# PowerAmplifier.net
KiCad netlist of a schematic drawn in Altium Designer
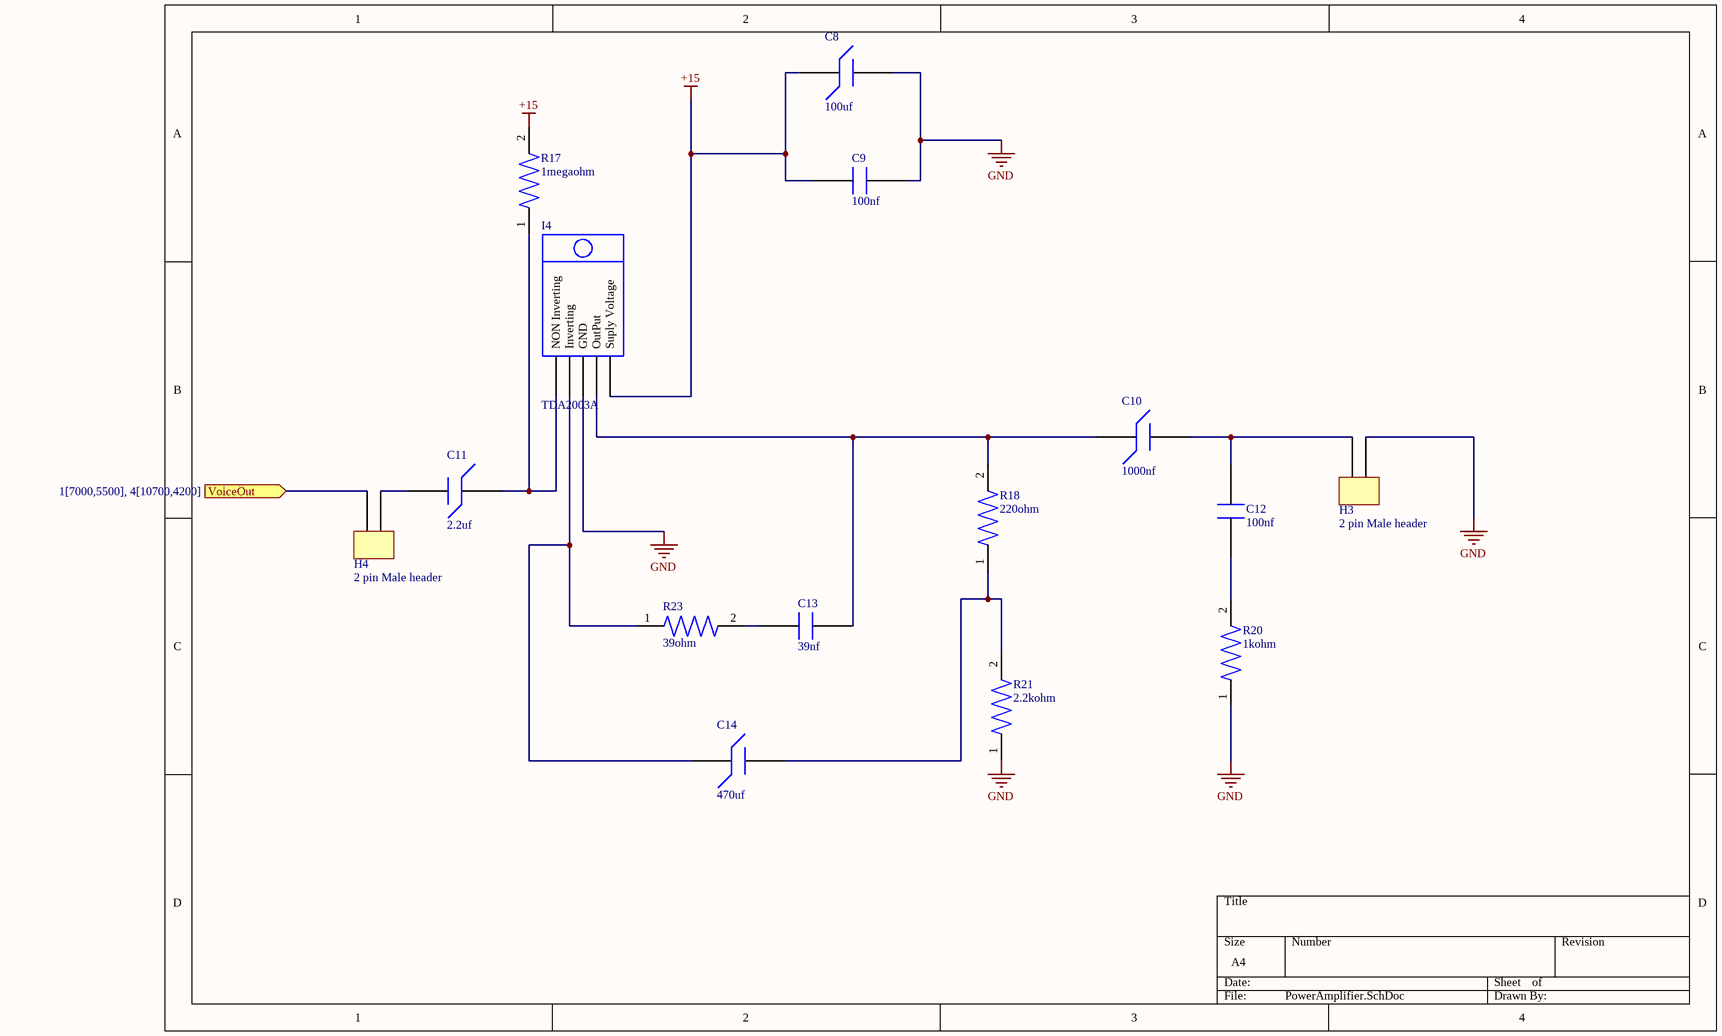
[diagram p0: PowerAmplifier.SchDoc]

(export (version "E")
  (design (tool "Eeschema 10.0.6"))
  (components
    (comp (ref "C8")
      (value "100uf")
      (footprint "Capasitor")
      (fields
        (field (name "MANUFACTURER") "Rubycon")
        (field (name "MANUFACTURER PART NUMBER") "35ZLH100MEFC6.3X11")
      )
      (libsource (lib "AudioAmplifierBasic") (part "35ZLH100MEFC6.3X11"))
    )
    (comp (ref "C9")
      (value "100nf")
      (footprint "ceramic Capacitor")
      (fields
        (field (name "MANUFACTURER") "Vishay BCcomponents")
        (field (name "MANUFACTURER PART NUMBER") "K104K20X7RK53H5G")
      )
      (libsource (lib "AudioAmplifierBasic") (part "K104K20X7RK53H5G"))
    )
    (comp (ref "C10")
      (value "1000nf")
      (footprint "Capasitor")
      (fields
        (field (name "MANUFACTURER") "Rubycon")
        (field (name "MANUFACTURER PART NUMBER") "10ZLH1000MEFC10X12.5")
      )
      (libsource (lib "AudioAmplifierBasic") (part "10ZLH1000MEFC10X12.5"))
    )
    (comp (ref "C11")
      (value "2.2uf")
      (footprint "Capasitor")
      (fields
        (field (name "MANUFACTURER") "Rubycon")
        (field (name "MANUFACTURER PART NUMBER") "400LLE2R2MEFC8X11.5")
      )
      (libsource (lib "AudioAmplifierBasic") (part "400LLE2R2MEFC8X11.5"))
    )
    (comp (ref "C12")
      (value "100nf")
      (footprint "ceramic Capacitor")
      (fields
        (field (name "MANUFACTURER") "Vishay BCcomponents")
        (field (name "MANUFACTURER PART NUMBER") "K104K20X7RK53H5G")
      )
      (libsource (lib "AudioAmplifierBasic") (part "K104K20X7RK53H5G"))
    )
    (comp (ref "C13")
      (value "39nf")
      (footprint "Ceramic Capacitor 2")
      (fields
        (field (name "MANUFACTURER") "KEMET")
        (field (name "MANUFACTURER PART NUMBER") "C320C393K3G5TA")
      )
      (libsource (lib "AudioAmplifierBasic") (part "C320C393K3G5TA"))
    )
    (comp (ref "C14")
      (value "470uf")
      (footprint "Capasitor")
      (description "Aluminum Electrolytic Capacitor, Polarized, Aluminum (wet), 16V, 20% +Tol, 20% -Tol, 470uF")
      (fields
        (field (name "MANUFACTURER") "Rubycon")
        (field (name "MANUFACTURER PART NUMBER") "16ZLJ470MTA8X11.5")
      )
      (libsource (lib "AudioAmplifierBasic") (part "16ZLJ470MTA8X11.5"))
    )
    (comp (ref "H3")
      (value "2 pin Male header")
      (footprint "2pin Male Heder")
      (fields
        (field (name "MANUFACTURER") "Wurth Electronics")
        (field (name "MANUFACTURER PART NUMBER") "61300211121")
      )
      (libsource (lib "AudioAmplifierBasic") (part "61300211121"))
    )
    (comp (ref "H4")
      (value "2 pin Male header")
      (footprint "2pin Male Heder")
      (fields
        (field (name "MANUFACTURER") "Wurth Electronics")
        (field (name "MANUFACTURER PART NUMBER") "61300211121")
      )
      (libsource (lib "AudioAmplifierBasic") (part "61300211121"))
    )
    (comp (ref "I4")
      (value "TDA2003A")
      (footprint "TDA2003AV")
      (description "Audio Amplifier, 12W, 1 Channel(s), 1 Func, Bipolar")
      (fields
        (field (name "MANUFACTURER") "STMicroelectronics")
        (field (name "MANUFACTURER PART NUMBER") "TDA2003AV")
      )
      (libsource (lib "AudioAmplifierBasic") (part "TDA2003AV"))
    )
    (comp (ref "R17")
      (value "1megaohm")
      (footprint "Resistor")
      (fields
        (field (name "MANUFACTURER") "Stackpole Electronics")
        (field (name "MANUFACTURER PART NUMBER") "CF14JT1M00")
        (field (name "TOLERANCE") "5%")
      )
      (libsource (lib "AudioAmplifierBasic") (part "CF14JT1M00"))
    )
    (comp (ref "R18")
      (value "220ohm")
      (footprint "Resistor")
      (description "RES SMD 220 OHM 1% 2W 4525")
      (fields (field (name "MANUFACTURER") "Riedon") (field (name "MANUFACTURER PART NUMBER") "S4-220RF1"))
      (libsource (lib "AudioAmplifierBasic") (part "S4-220RF1"))
    )
    (comp (ref "R20")
      (value "1kohm")
      (footprint "Resistor")
      (description "Fixed Resistor, Carbon Film, 0.25W, 1000ohm, 350V, 5% +/-Tol, -400,0ppm/Cel, Through Hole Mount")
      (fields
        (field (name "MANUFACTURER") "Stackpole Electronics")
        (field (name "MANUFACTURER PART NUMBER") "CF14JT1K00")
      )
      (libsource (lib "AudioAmplifierBasic") (part "CF14JT1K00"))
    )
    (comp (ref "R21")
      (value "2.2kohm")
      (footprint "Resistor")
      (fields
        (field (name "MANUFACTURER") "Ohmite")
        (field (name "MANUFACTURER PART NUMBER") "OY222KE")
        (field (name "TOLERANCE") "10%")
      )
      (libsource (lib "AudioAmplifierBasic") (part "OY222KE"))
    )
    (comp (ref "R23")
      (value "39ohm")
      (footprint "Resistor")
      (description "Fixed Resistor, Metal Oxide Film, 1W, 39ohm, 350V, 5% +/-Tol, 350ppm/Cel, Through Hole Mount")
      (fields
        (field (name "MANUFACTURER") "TE Connectivity")
        (field (name "MANUFACTURER PART NUMBER") "ROX1SJ39R")
      )
      (libsource (lib "AudioAmplifierBasic") (part "ROX1SJ39R"))
    )
  )
  (nets
    (net (code "1") (name "+15") (class "Default")
      (node (ref "C8") (pin "2") (pinfunction "2_2") (pintype "passive"))
      (node (ref "C9") (pin "1") (pinfunction "6_1") (pintype "passive"))
      (node (ref "I4") (pin "5") (pinfunction "Suply_Voltage_5") (pintype "passive"))
      (node (ref "R17") (pin "2") (pinfunction "2_2") (pintype "passive"))
    )
    (net (code "2") (name "/VoiceOut") (class "Default")
      (node (ref "H4") (pin "2") (pinfunction "11_2") (pintype "passive"))
    )
    (net (code "3") (name "GND") (class "Default")
      (node (ref "C8") (pin "1") (pinfunction "1_1") (pintype "passive"))
      (node (ref "C9") (pin "2") (pinfunction "7_2") (pintype "passive"))
      (node (ref "H3") (pin "1") (pinfunction "10_1") (pintype "passive"))
      (node (ref "I4") (pin "3") (pinfunction "GND_3") (pintype "passive"))
      (node (ref "R20") (pin "1") (pinfunction "1_1") (pintype "passive"))
      (node (ref "R21") (pin "1") (pinfunction "1_1") (pintype "passive"))
    )
    (net (code "4") (name "Net-(C12-6)") (class "Default")
      (node (ref "C12") (pin "1") (pinfunction "6_1") (pintype "passive"))
      (node (ref "R20") (pin "2") (pinfunction "2_2") (pintype "passive"))
    )
    (net (code "5") (name "Net-(C12-7)") (class "Default")
      (node (ref "C10") (pin "1") (pinfunction "1_1") (pintype "passive"))
      (node (ref "C12") (pin "2") (pinfunction "7_2") (pintype "passive"))
      (node (ref "H3") (pin "2") (pinfunction "11_2") (pintype "passive"))
    )
    (net (code "6") (name "Net-(C13-Pad1)") (class "Default")
      (node (ref "C13") (pin "1") (pinfunction "1_1") (pintype "passive"))
      (node (ref "R23") (pin "2") (pinfunction "2_2") (pintype "passive"))
    )
    (net (code "7") (name "Net-(C14-Pad1)") (class "Default")
      (node (ref "C14") (pin "1") (pinfunction "1_1") (pintype "passive"))
      (node (ref "R18") (pin "1") (pinfunction "1_1") (pintype "passive"))
      (node (ref "R21") (pin "2") (pinfunction "2_2") (pintype "passive"))
    )
    (net (code "8") (name "Net-(H4-10)") (class "Default")
      (node (ref "C11") (pin "1") (pinfunction "1_1") (pintype "passive"))
      (node (ref "H4") (pin "1") (pinfunction "10_1") (pintype "passive"))
    )
    (net (code "9") (name "Net-(I4-Inverting)") (class "Default")
      (node (ref "C14") (pin "2") (pinfunction "2_2") (pintype "passive"))
      (node (ref "I4") (pin "2") (pinfunction "Inverting_2") (pintype "passive"))
      (node (ref "R23") (pin "1") (pinfunction "1_1") (pintype "passive"))
    )
    (net (code "10") (name "Net-(I4-NON_Inverting)") (class "Default")
      (node (ref "C11") (pin "2") (pinfunction "2_2") (pintype "passive"))
      (node (ref "I4") (pin "1") (pinfunction "NON_Inverting_1") (pintype "passive"))
      (node (ref "R17") (pin "1") (pinfunction "1_1") (pintype "passive"))
    )
    (net (code "11") (name "Net-(I4-OutPut)") (class "Default")
      (node (ref "C10") (pin "2") (pinfunction "2_2") (pintype "passive"))
      (node (ref "C13") (pin "2") (pinfunction "2_2") (pintype "passive"))
      (node (ref "I4") (pin "4") (pinfunction "OutPut_4") (pintype "passive"))
      (node (ref "R18") (pin "2") (pinfunction "2_2") (pintype "passive"))
    )
  )
)
